# tirasRGB.net
KiCad netlist of a schematic drawn in EAGLE
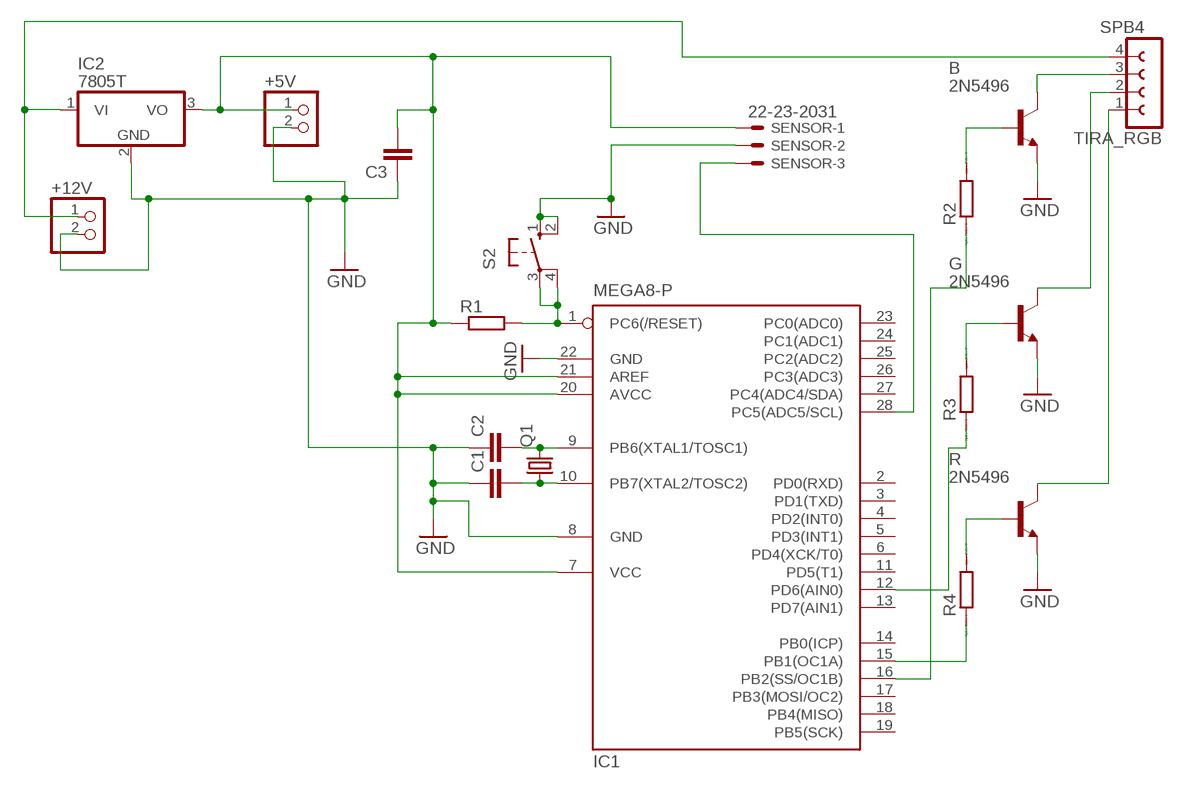
[diagram p0: schematic, sheet 1]

(export (version "E")
  (design (tool "Eeschema 10.0.6"))
  (components
    (comp (ref "+5V")
      (value "PINHD-1X2")
      (footprint "eagle-import:1X02")
      (libsource (lib "eagle-import") (part "PINHD-1X2"))
    )
    (comp (ref "+12V")
      (value "PINHD-1X2")
      (footprint "eagle-import:1X02")
      (libsource (lib "eagle-import") (part "PINHD-1X2"))
    )
    (comp (ref "B")
      (value "2N5496")
      (footprint "eagle-import:TO220")
      (libsource (lib "eagle-import") (part "2N5496"))
    )
    (comp (ref "C1")
      (value "C2,5-3")
      (footprint "eagle-import:C2.5-3")
      (libsource (lib "eagle-import") (part "C2,5-3"))
    )
    (comp (ref "C2")
      (value "C2,5-3")
      (footprint "eagle-import:C2.5-3")
      (libsource (lib "eagle-import") (part "C2,5-3"))
    )
    (comp (ref "C3")
      (value "C2,5-3")
      (footprint "eagle-import:C2.5-3")
      (libsource (lib "eagle-import") (part "C2,5-3"))
    )
    (comp (ref "G")
      (value "2N5496")
      (footprint "eagle-import:TO220")
      (libsource (lib "eagle-import") (part "2N5496"))
    )
    (comp (ref "IC1")
      (value "MEGA8-P")
      (footprint "eagle-import:DIL28-3")
      (libsource (lib "eagle-import") (part "MEGA8-P"))
    )
    (comp (ref "IC2")
      (value "7805T")
      (footprint "eagle-import:TO220H")
      (libsource (lib "eagle-import") (part "78T05"))
    )
    (comp (ref "Q1")
      (value "CRYSTALTC26V")
      (footprint "eagle-import:TC26V")
      (libsource (lib "eagle-import") (part "CRYSTALTC26V"))
    )
    (comp (ref "R")
      (value "2N5496")
      (footprint "eagle-import:TO220")
      (libsource (lib "eagle-import") (part "2N5496"))
    )
    (comp (ref "R1")
      (value "R-EU_0204/5")
      (footprint "eagle-import:0204_5")
      (libsource (lib "eagle-import") (part "R-EU_0204/5"))
    )
    (comp (ref "R2")
      (value "R0207/10")
      (footprint "eagle-import:0207_10")
      (libsource (lib "eagle-import") (part "R0207/10"))
    )
    (comp (ref "R3")
      (value "R0207/10")
      (footprint "eagle-import:0207_10")
      (libsource (lib "eagle-import") (part "R0207/10"))
    )
    (comp (ref "R4")
      (value "R0207/10")
      (footprint "eagle-import:0207_10")
      (libsource (lib "eagle-import") (part "R0207/10"))
    )
    (comp (ref "S2")
      (value "10-XX")
      (footprint "eagle-import:B3F-10XX")
      (fields (field (name "MPN") "B3F-1000"))
      (libsource (lib "eagle-import") (part "10-XX"))
    )
    (comp (ref "SENSOR")
      (value "22-23-2031")
      (footprint "eagle-import:22-23-2031")
      (fields (field (name "MF") "MOLEX"))
      (libsource (lib "eagle-import") (part "22-23-2031"))
    )
    (comp (ref "TIRA_RGB")
      (value "SPB4")
      (footprint "eagle-import:SPB4")
      (libsource (lib "eagle-import") (part "SPB4"))
    )
  )
  (nets
    (net (code "1") (name "GND") (class "Default")
      (node (ref "+12V") (pin "2") (pinfunction "2_2") (pintype "passive"))
      (node (ref "+5V") (pin "2") (pinfunction "2_2") (pintype "passive"))
      (node (ref "B") (pin "3") (pinfunction "E_3") (pintype "passive"))
      (node (ref "C1") (pin "1") (pinfunction "1_1") (pintype "passive"))
      (node (ref "C2") (pin "1") (pinfunction "1_1") (pintype "passive"))
      (node (ref "C3") (pin "1") (pinfunction "1_1") (pintype "passive"))
      (node (ref "G") (pin "3") (pinfunction "E_3") (pintype "passive"))
      (node (ref "IC1") (pin "22") (pinfunction "GND_22") (pintype "power_in"))
      (node (ref "IC1") (pin "8") (pinfunction "GND_8") (pintype "power_in"))
      (node (ref "IC2") (pin "2") (pinfunction "GND_2") (pintype "passive"))
      (node (ref "R") (pin "3") (pinfunction "E_3") (pintype "passive"))
      (node (ref "S2") (pin "1") (pinfunction "S_1") (pintype "passive"))
      (node (ref "S2") (pin "2") (pinfunction "S1_2") (pintype "passive"))
      (node (ref "SENSOR") (pin "2") (pinfunction "S_2") (pintype "passive"))
    )
    (net (code "2") (name "Net-(B-B)") (class "Default")
      (node (ref "B") (pin "1") (pinfunction "B_1") (pintype "passive"))
      (node (ref "R2") (pin "2") (pinfunction "2_2") (pintype "passive"))
    )
    (net (code "3") (name "Net-(B-C)") (class "Default")
      (node (ref "B") (pin "2") (pinfunction "C_2") (pintype "passive"))
      (node (ref "TIRA_RGB") (pin "3") (pinfunction "3_3") (pintype "passive"))
    )
    (net (code "4") (name "Net-(G-B)") (class "Default")
      (node (ref "G") (pin "1") (pinfunction "B_1") (pintype "passive"))
      (node (ref "R3") (pin "2") (pinfunction "2_2") (pintype "passive"))
    )
    (net (code "5") (name "Net-(G-C)") (class "Default")
      (node (ref "G") (pin "2") (pinfunction "C_2") (pintype "passive"))
      (node (ref "TIRA_RGB") (pin "2") (pinfunction "2_2") (pintype "passive"))
    )
    (net (code "6") (name "Net-(IC1-AREF)") (class "Default")
      (node (ref "+5V") (pin "1") (pinfunction "1_1") (pintype "passive"))
      (node (ref "C3") (pin "2") (pinfunction "2_2") (pintype "passive"))
      (node (ref "IC1") (pin "20") (pinfunction "AVCC_20") (pintype "power_in"))
      (node (ref "IC1") (pin "21") (pinfunction "AREF_21") (pintype "passive"))
      (node (ref "IC1") (pin "7") (pinfunction "VCC_7") (pintype "power_in"))
      (node (ref "IC2") (pin "3") (pinfunction "VO_3") (pintype "passive"))
      (node (ref "R1") (pin "1") (pinfunction "1_1") (pintype "passive"))
      (node (ref "SENSOR") (pin "1") (pinfunction "S_1") (pintype "passive"))
    )
    (net (code "7") (name "Net-(IC1-PB1(OC1A))") (class "Default")
      (node (ref "IC1") (pin "15") (pinfunction "PB1(OC1A)_15") (pintype "bidirectional"))
      (node (ref "R4") (pin "1") (pinfunction "1_1") (pintype "passive"))
    )
    (net (code "8") (name "Net-(IC1-PB2(SS{slash}OC1B))") (class "Default")
      (node (ref "IC1") (pin "16") (pinfunction "PB2(SS/OC1B)_16") (pintype "bidirectional"))
      (node (ref "R2") (pin "1") (pinfunction "1_1") (pintype "passive"))
    )
    (net (code "9") (name "Net-(IC1-PB6(XTAL1{slash}TOSC1))") (class "Default")
      (node (ref "C2") (pin "2") (pinfunction "2_2") (pintype "passive"))
      (node (ref "IC1") (pin "9") (pinfunction "PB6(XTAL1/TOSC1)_9") (pintype "bidirectional"))
      (node (ref "Q1") (pin "2") (pinfunction "2_2") (pintype "passive"))
    )
    (net (code "10") (name "Net-(IC1-PB7(XTAL2{slash}TOSC2))") (class "Default")
      (node (ref "C1") (pin "2") (pinfunction "2_2") (pintype "passive"))
      (node (ref "IC1") (pin "10") (pinfunction "PB7(XTAL2/TOSC2)_10") (pintype "bidirectional"))
      (node (ref "Q1") (pin "1") (pinfunction "1_1") (pintype "passive"))
    )
    (net (code "11") (name "Net-(IC1-PC5(ADC5{slash}SCL))") (class "Default")
      (node (ref "IC1") (pin "28") (pinfunction "PC5(ADC5/SCL)_28") (pintype "bidirectional"))
      (node (ref "SENSOR") (pin "3") (pinfunction "S_3") (pintype "passive"))
    )
    (net (code "12") (name "Net-(IC1-PC6({slash}RESET))") (class "Default")
      (node (ref "IC1") (pin "1") (pinfunction "PC6(/RESET)_1") (pintype "bidirectional"))
      (node (ref "R1") (pin "2") (pinfunction "2_2") (pintype "passive"))
      (node (ref "S2") (pin "3") (pinfunction "P_3") (pintype "passive"))
      (node (ref "S2") (pin "4") (pinfunction "P1_4") (pintype "passive"))
    )
    (net (code "13") (name "Net-(IC1-PD6(AIN0))") (class "Default")
      (node (ref "IC1") (pin "12") (pinfunction "PD6(AIN0)_12") (pintype "bidirectional"))
      (node (ref "R3") (pin "1") (pinfunction "1_1") (pintype "passive"))
    )
    (net (code "14") (name "Net-(IC2-VI)") (class "Default")
      (node (ref "+12V") (pin "1") (pinfunction "1_1") (pintype "passive"))
      (node (ref "IC2") (pin "1") (pinfunction "VI_1") (pintype "input"))
      (node (ref "TIRA_RGB") (pin "4") (pinfunction "4_4") (pintype "passive"))
    )
    (net (code "15") (name "Net-(R-B)") (class "Default")
      (node (ref "R") (pin "1") (pinfunction "B_1") (pintype "passive"))
      (node (ref "R4") (pin "2") (pinfunction "2_2") (pintype "passive"))
    )
    (net (code "16") (name "Net-(R-C)") (class "Default")
      (node (ref "R") (pin "2") (pinfunction "C_2") (pintype "passive"))
      (node (ref "TIRA_RGB") (pin "1") (pinfunction "1_1") (pintype "passive"))
    )
    (net (code "17") (name "unconnected-(IC1-PB0(ICP)-Pad14)") (class "Default")
      (node (ref "IC1") (pin "14") (pinfunction "PB0(ICP)_14") (pintype "bidirectional"))
    )
    (net (code "18") (name "unconnected-(IC1-PB3(MOSI{slash}OC2)-Pad17)") (class "Default")
      (node (ref "IC1") (pin "17") (pinfunction "PB3(MOSI/OC2)_17") (pintype "bidirectional"))
    )
    (net (code "19") (name "unconnected-(IC1-PB4(MISO)-Pad18)") (class "Default")
      (node (ref "IC1") (pin "18") (pinfunction "PB4(MISO)_18") (pintype "bidirectional"))
    )
    (net (code "20") (name "unconnected-(IC1-PB5(SCK)-Pad19)") (class "Default")
      (node (ref "IC1") (pin "19") (pinfunction "PB5(SCK)_19") (pintype "bidirectional"))
    )
    (net (code "21") (name "unconnected-(IC1-PC0(ADC0)-Pad23)") (class "Default")
      (node (ref "IC1") (pin "23") (pinfunction "PC0(ADC0)_23") (pintype "bidirectional"))
    )
    (net (code "22") (name "unconnected-(IC1-PC1(ADC1)-Pad24)") (class "Default")
      (node (ref "IC1") (pin "24") (pinfunction "PC1(ADC1)_24") (pintype "bidirectional"))
    )
    (net (code "23") (name "unconnected-(IC1-PC2(ADC2)-Pad25)") (class "Default")
      (node (ref "IC1") (pin "25") (pinfunction "PC2(ADC2)_25") (pintype "bidirectional"))
    )
    (net (code "24") (name "unconnected-(IC1-PC3(ADC3)-Pad26)") (class "Default")
      (node (ref "IC1") (pin "26") (pinfunction "PC3(ADC3)_26") (pintype "bidirectional"))
    )
    (net (code "25") (name "unconnected-(IC1-PC4(ADC4{slash}SDA)-Pad27)") (class "Default")
      (node (ref "IC1") (pin "27") (pinfunction "PC4(ADC4/SDA)_27") (pintype "bidirectional"))
    )
    (net (code "26") (name "unconnected-(IC1-PD0(RXD)-Pad2)") (class "Default")
      (node (ref "IC1") (pin "2") (pinfunction "PD0(RXD)_2") (pintype "bidirectional"))
    )
    (net (code "27") (name "unconnected-(IC1-PD1(TXD)-Pad3)") (class "Default")
      (node (ref "IC1") (pin "3") (pinfunction "PD1(TXD)_3") (pintype "bidirectional"))
    )
    (net (code "28") (name "unconnected-(IC1-PD2(INT0)-Pad4)") (class "Default")
      (node (ref "IC1") (pin "4") (pinfunction "PD2(INT0)_4") (pintype "bidirectional"))
    )
    (net (code "29") (name "unconnected-(IC1-PD3(INT1)-Pad5)") (class "Default")
      (node (ref "IC1") (pin "5") (pinfunction "PD3(INT1)_5") (pintype "bidirectional"))
    )
    (net (code "30") (name "unconnected-(IC1-PD4(XCK{slash}T0)-Pad6)") (class "Default")
      (node (ref "IC1") (pin "6") (pinfunction "PD4(XCK/T0)_6") (pintype "bidirectional"))
    )
    (net (code "31") (name "unconnected-(IC1-PD5(T1)-Pad11)") (class "Default")
      (node (ref "IC1") (pin "11") (pinfunction "PD5(T1)_11") (pintype "bidirectional"))
    )
    (net (code "32") (name "unconnected-(IC1-PD7(AIN1)-Pad13)") (class "Default")
      (node (ref "IC1") (pin "13") (pinfunction "PD7(AIN1)_13") (pintype "bidirectional"))
    )
  )
)
